# LPCB230_-_TC_CHANNEL.net
KiCad netlist of a schematic drawn in Altium Designer
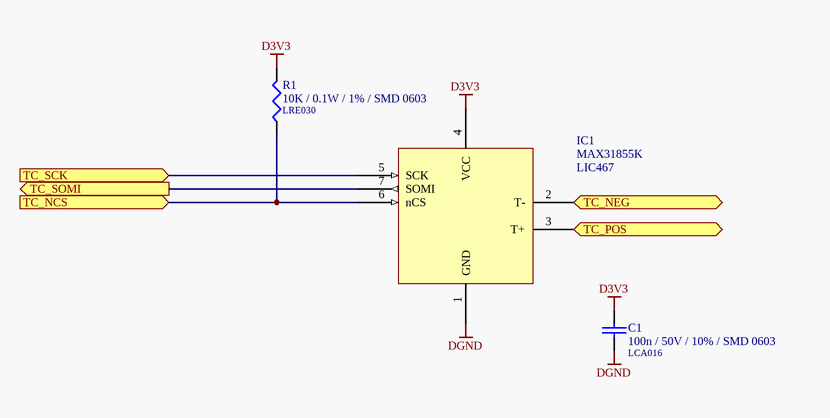
[diagram p0: LPCB230 - TC CHANNEL.SchDoc]

(export (version "E")
  (design (tool "Eeschema 10.0.6"))
  (components
    (comp (ref "C1")
      (value "100n / 50V / 10% / SMD 0603")
      (footprint "LFP011__CC1608-0603-IPC7351_B")
      (description "Capacitor, Ceramic Chip, 100nF (0.1uF), 50V, 5%, SMD 0603 [LCA016]")
      (fields (field (name "LDL_NUMBER") "LCA016"))
      (libsource (lib "LDL_Capacitors") (part "100n / 50V / 10% / SMD 0603"))
    )
    (comp (ref "IC1")
      (value "MAX31855K")
      (footprint "LFP017__SO-G8/Y1.9")
      (description "IC, Thermocouple Interface, Type K, SMD SOIC-8 [LIC467]")
      (fields (field (name "LDL_NUMBER") "LIC467"))
      (libsource (lib "LDL_Semiconductors") (part "MAX31855K"))
    )
    (comp (ref "R1")
      (value "10K / 0.1W / 1% / SMD 0603")
      (footprint "LFP020__CR1608-0603-IPC7351_B")
      (description "Resistor, Ceramic Chip, 10K, 0.1W, 1%, SMD 0603 [LRE030]")
      (fields (field (name "LDL_NUMBER") "LRE030"))
      (libsource (lib "LDL_Resistors") (part "10K / 0.1W / 1% / SMD 0603"))
    )
  )
  (nets
    (net (code "1") (name "/TC_NCS") (class "Default")
      (node (ref "IC1") (pin "6") (pinfunction "nCS_6") (pintype "input"))
      (node (ref "R1") (pin "1") (pintype "passive"))
    )
    (net (code "2") (name "/TC_NEG") (class "Default")
      (node (ref "IC1") (pin "2") (pinfunction "T-_2") (pintype "passive"))
    )
    (net (code "3") (name "/TC_POS") (class "Default")
      (node (ref "IC1") (pin "3") (pinfunction "T+_3") (pintype "passive"))
    )
    (net (code "4") (name "/TC_SCK") (class "Default")
      (node (ref "IC1") (pin "5") (pinfunction "SCK_5") (pintype "input"))
    )
    (net (code "5") (name "/TC_SOMI") (class "Default")
      (node (ref "IC1") (pin "7") (pinfunction "SOMI_7") (pintype "output"))
    )
    (net (code "6") (name "D3V3") (class "Default")
      (node (ref "C1") (pin "1") (pintype "passive"))
      (node (ref "IC1") (pin "4") (pinfunction "VCC_4") (pintype "power_in"))
      (node (ref "R1") (pin "2") (pintype "passive"))
    )
    (net (code "7") (name "DGND") (class "Default")
      (node (ref "C1") (pin "2") (pintype "passive"))
      (node (ref "IC1") (pin "1") (pinfunction "GND_1") (pintype "power_in"))
    )
  )
)
